# AmbaSat-1_Satellite.net
KiCad netlist of a schematic drawn in EAGLE
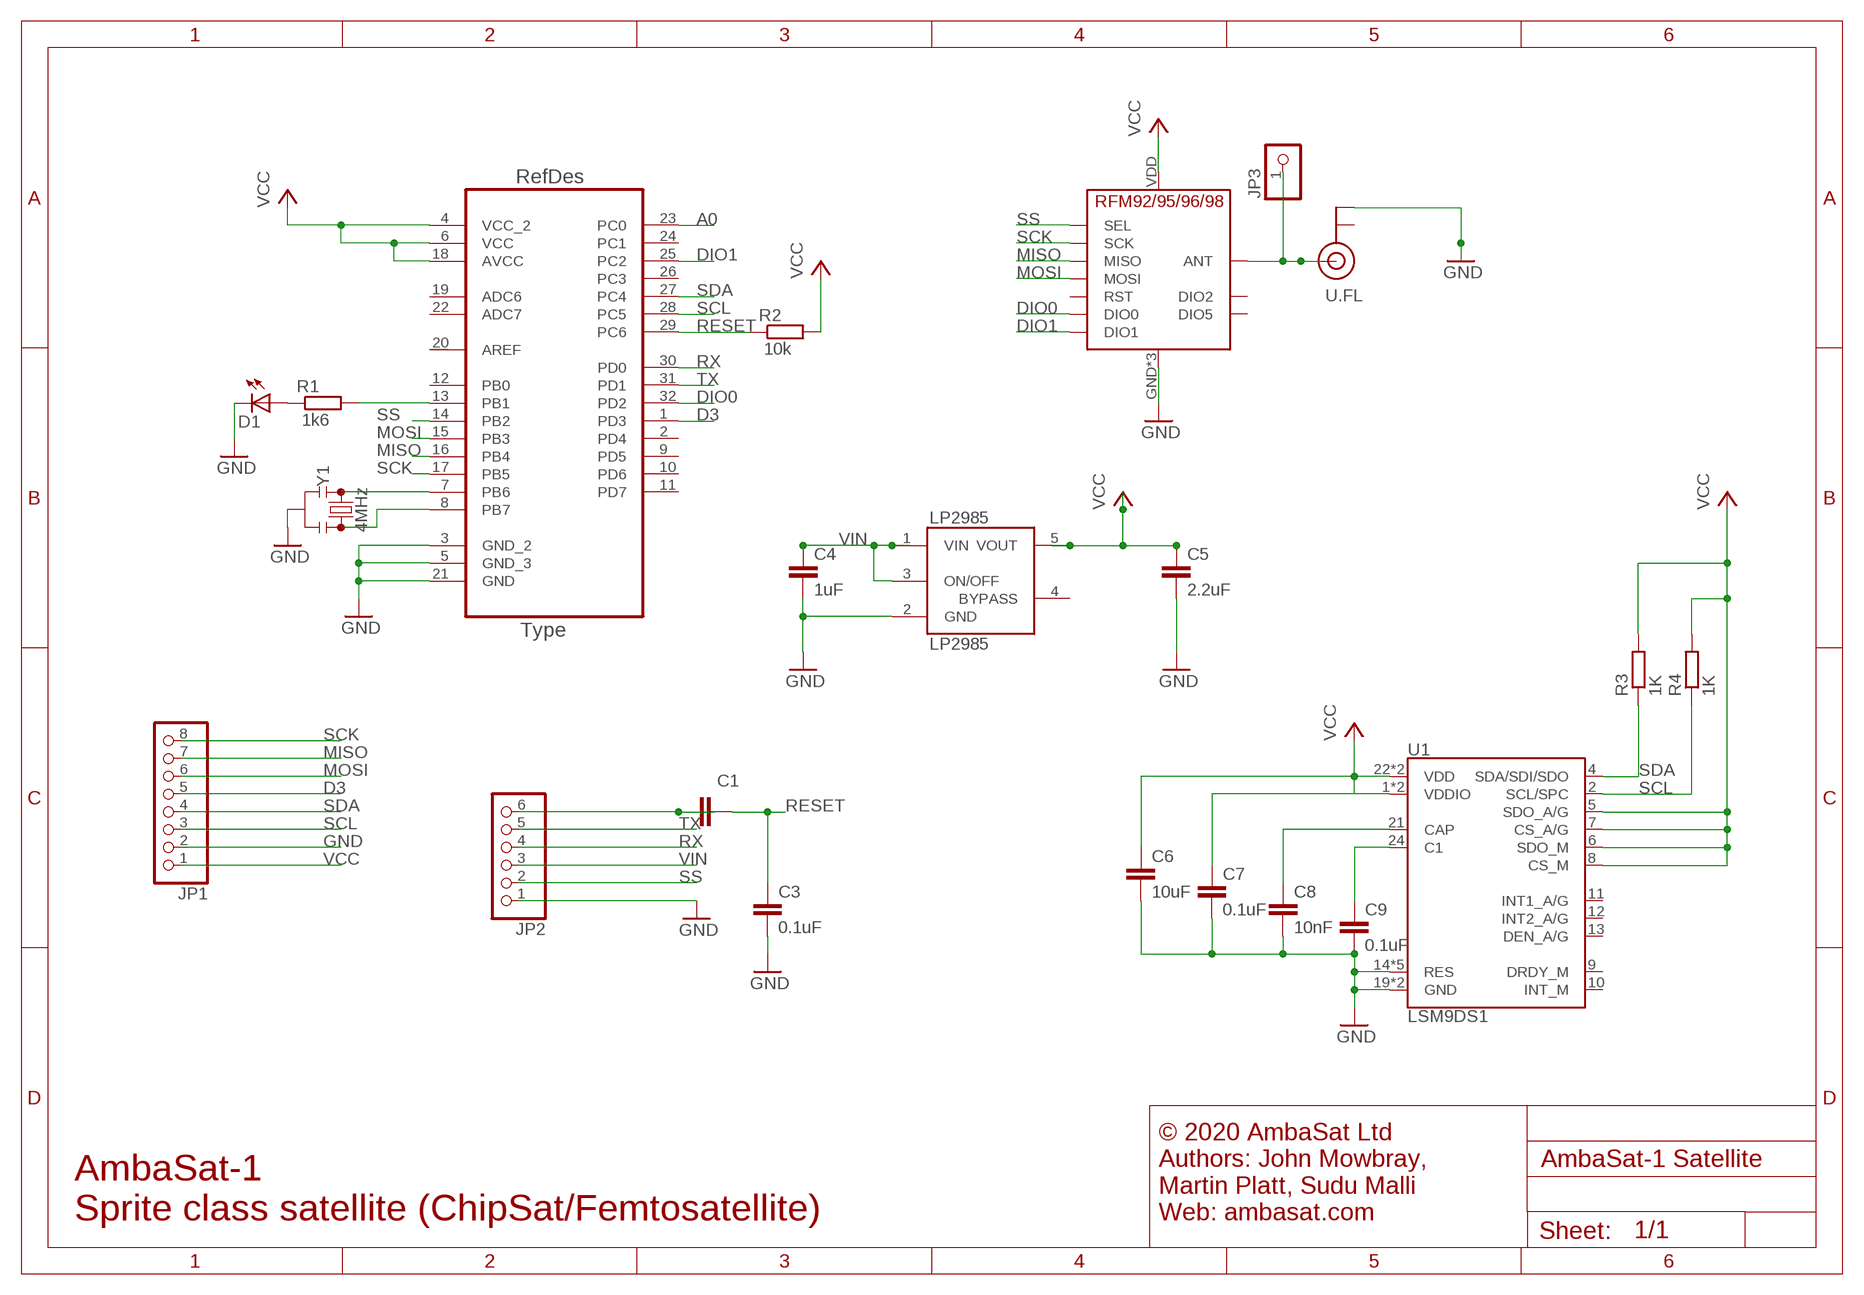
[diagram p0: schematic, sheet 1]

(export (version "E")
  (design (tool "Eeschema 10.0.6"))
  (components
    (comp (ref "ATMEGA328P-AU")
      (value "ATMEGA328P-AU")
      (footprint "eagle-import:QFP80P900X900X120-32N")
      (libsource (lib "eagle-import") (part "ATMEGA328P-AU"))
    )
    (comp (ref "C1")
      (value "1uF")
      (footprint "eagle-import:C0805K")
      (libsource (lib "eagle-import") (part "C-EUC0805K"))
    )
    (comp (ref "C3")
      (value "0.1uF")
      (footprint "eagle-import:C0805K")
      (libsource (lib "eagle-import") (part "C-EUC0805K"))
    )
    (comp (ref "C4")
      (value "1uF")
      (footprint "eagle-import:C0805K")
      (libsource (lib "eagle-import") (part "C-EUC0805K"))
    )
    (comp (ref "C5")
      (value "2.2uF")
      (footprint "eagle-import:C0805K")
      (libsource (lib "eagle-import") (part "C-EUC0805K"))
    )
    (comp (ref "C6")
      (value "10uF")
      (footprint "eagle-import:C0805K")
      (libsource (lib "eagle-import") (part "C-EUC0805K"))
    )
    (comp (ref "C7")
      (value "0.1uF")
      (footprint "eagle-import:C0805K")
      (libsource (lib "eagle-import") (part "C-EUC0805K"))
    )
    (comp (ref "C8")
      (value "10nF")
      (footprint "eagle-import:C0805K")
      (libsource (lib "eagle-import") (part "C-EUC0805K"))
    )
    (comp (ref "C9")
      (value "0.1uF")
      (footprint "eagle-import:C0805K")
      (libsource (lib "eagle-import") (part "C-EUC0805K"))
    )
    (comp (ref "D1")
      (value "LEDCHIP-LED0805")
      (footprint "eagle-import:CHIP-LED0805")
      (libsource (lib "eagle-import") (part "LEDCHIP-LED0805"))
    )
    (comp (ref "JP1")
      (value "PINHD-1X8")
      (footprint "eagle-import:1X08")
      (libsource (lib "eagle-import") (part "PINHD-1X8"))
    )
    (comp (ref "JP2")
      (value "PINHD-1X6")
      (footprint "eagle-import:1X06")
      (libsource (lib "eagle-import") (part "PINHD-1X6"))
    )
    (comp (ref "JP3")
      (value "HEADER-1X1ROUND")
      (footprint "eagle-import:1X01_ROUND")
      (libsource (lib "eagle-import") (part "HEADER-1X1ROUND"))
    )
    (comp (ref "LP2985")
      (value "LP2985AIM5-3.3")
      (footprint "eagle-import:SOT25")
      (libsource (lib "eagle-import") (part "LP2985AIM5-3.3"))
    )
    (comp (ref "R1")
      (value "1k6")
      (footprint "eagle-import:M0805")
      (libsource (lib "eagle-import") (part "R-EU_M0805"))
    )
    (comp (ref "R2")
      (value "10k")
      (footprint "eagle-import:M0805")
      (libsource (lib "eagle-import") (part "R-EU_M0805"))
    )
    (comp (ref "R3")
      (value "1K")
      (footprint "eagle-import:M0805")
      (libsource (lib "eagle-import") (part "R-EU_M0805"))
    )
    (comp (ref "R4")
      (value "1K")
      (footprint "eagle-import:M0805")
      (libsource (lib "eagle-import") (part "R-EU_M0805"))
    )
    (comp (ref "RFM95")
      (value "RFM95")
      (footprint "eagle-import:RFM95")
      (libsource (lib "eagle-import") (part "RFM95"))
    )
    (comp (ref "U.FL")
      (value "U.FL")
      (footprint "eagle-import:U.FL")
      (libsource (lib "eagle-import") (part "U.FL"))
    )
    (comp (ref "U1")
      (value "LSM9DS1")
      (footprint "eagle-import:LGA24-8X4")
      (libsource (lib "eagle-import") (part "LSM9DS1"))
    )
    (comp (ref "Y1")
      (value "4MHz")
      (footprint "eagle-import:RESONATOR-SMD-4.5X2.0")
      (libsource (lib "eagle-import") (part "RESONATOR-4MHZSMD-4.5X2"))
    )
  )
  (nets
    (net (code "1") (name "/A0") (class "Default")
      (node (ref "ATMEGA328P-AU") (pin "23") (pinfunction "PC0_23") (pintype "bidirectional"))
    )
    (net (code "2") (name "/BYPASS") (class "Default")
      (node (ref "LP2985") (pin "4") (pinfunction "BYPASS_4") (pintype "power_in"))
    )
    (net (code "3") (name "/D3") (class "Default")
      (node (ref "ATMEGA328P-AU") (pin "1") (pinfunction "PD3_1") (pintype "bidirectional"))
      (node (ref "JP1") (pin "5") (pinfunction "5_5") (pintype "passive"))
    )
    (net (code "4") (name "/DIO0") (class "Default")
      (node (ref "ATMEGA328P-AU") (pin "32") (pinfunction "PD2_32") (pintype "bidirectional"))
      (node (ref "RFM95") (pin "DIO0") (pinfunction "DIO0_DIO0") (pintype "open_collector"))
    )
    (net (code "5") (name "/DIO1") (class "Default")
      (node (ref "ATMEGA328P-AU") (pin "25") (pinfunction "PC2_25") (pintype "bidirectional"))
      (node (ref "RFM95") (pin "DIO1") (pinfunction "DIO1_DIO1") (pintype "open_collector"))
    )
    (net (code "6") (name "/MISO") (class "Default")
      (node (ref "ATMEGA328P-AU") (pin "16") (pinfunction "PB4_16") (pintype "bidirectional"))
      (node (ref "JP1") (pin "7") (pinfunction "7_7") (pintype "passive"))
      (node (ref "RFM95") (pin "MISO") (pinfunction "MISO_MISO") (pintype "input"))
    )
    (net (code "7") (name "/MOSI") (class "Default")
      (node (ref "ATMEGA328P-AU") (pin "15") (pinfunction "PB3_15") (pintype "bidirectional"))
      (node (ref "JP1") (pin "6") (pinfunction "6_6") (pintype "passive"))
      (node (ref "RFM95") (pin "MOSI") (pinfunction "MOSI_MOSI") (pintype "output"))
    )
    (net (code "8") (name "/RESET") (class "Default")
      (node (ref "ATMEGA328P-AU") (pin "29") (pinfunction "PC6_29") (pintype "bidirectional"))
      (node (ref "C1") (pin "1") (pinfunction "1_1") (pintype "passive"))
      (node (ref "C3") (pin "1") (pinfunction "1_1") (pintype "passive"))
      (node (ref "R2") (pin "1") (pinfunction "1_1") (pintype "passive"))
    )
    (net (code "9") (name "/RX") (class "Default")
      (node (ref "ATMEGA328P-AU") (pin "30") (pinfunction "PD0_30") (pintype "bidirectional"))
      (node (ref "JP2") (pin "4") (pinfunction "4_4") (pintype "passive"))
    )
    (net (code "10") (name "/SCK") (class "Default")
      (node (ref "ATMEGA328P-AU") (pin "17") (pinfunction "PB5_17") (pintype "bidirectional"))
      (node (ref "JP1") (pin "8") (pinfunction "8_8") (pintype "passive"))
      (node (ref "RFM95") (pin "SCK") (pinfunction "SCK_SCK") (pintype "input"))
    )
    (net (code "11") (name "/SCL") (class "Default")
      (node (ref "ATMEGA328P-AU") (pin "28") (pinfunction "PC5_28") (pintype "bidirectional"))
      (node (ref "JP1") (pin "3") (pinfunction "3_3") (pintype "passive"))
      (node (ref "R4") (pin "1") (pinfunction "1_1") (pintype "passive"))
      (node (ref "U1") (pin "2") (pinfunction "SCL/SPC_2") (pintype "bidirectional"))
    )
    (net (code "12") (name "/SDA") (class "Default")
      (node (ref "ATMEGA328P-AU") (pin "27") (pinfunction "PC4_27") (pintype "bidirectional"))
      (node (ref "JP1") (pin "4") (pinfunction "4_4") (pintype "passive"))
      (node (ref "R3") (pin "1") (pinfunction "1_1") (pintype "passive"))
      (node (ref "U1") (pin "4") (pinfunction "SDA/SDI/SDO_4") (pintype "bidirectional"))
    )
    (net (code "13") (name "/SS") (class "Default")
      (node (ref "ATMEGA328P-AU") (pin "14") (pinfunction "PB2_14") (pintype "bidirectional"))
      (node (ref "JP2") (pin "2") (pinfunction "2_2") (pintype "passive"))
      (node (ref "RFM95") (pin "NSS") (pinfunction "SEL_NSS") (pintype "input"))
    )
    (net (code "14") (name "/TX") (class "Default")
      (node (ref "ATMEGA328P-AU") (pin "31") (pinfunction "PD1_31") (pintype "bidirectional"))
      (node (ref "JP2") (pin "5") (pinfunction "5_5") (pintype "passive"))
    )
    (net (code "15") (name "/VIN") (class "Default")
      (node (ref "C4") (pin "1") (pinfunction "1_1") (pintype "passive"))
      (node (ref "JP2") (pin "3") (pinfunction "3_3") (pintype "passive"))
      (node (ref "LP2985") (pin "1") (pinfunction "VIN_1") (pintype "power_in"))
      (node (ref "LP2985") (pin "3") (pinfunction "ON/OFF_3") (pintype "input"))
    )
    (net (code "16") (name "GND") (class "Default")
      (node (ref "ATMEGA328P-AU") (pin "21") (pinfunction "GND_21") (pintype "passive"))
      (node (ref "ATMEGA328P-AU") (pin "3") (pinfunction "GND_2_3") (pintype "passive"))
      (node (ref "ATMEGA328P-AU") (pin "5") (pinfunction "GND_3_5") (pintype "passive"))
      (node (ref "C3") (pin "2") (pinfunction "2_2") (pintype "passive"))
      (node (ref "C4") (pin "2") (pinfunction "2_2") (pintype "passive"))
      (node (ref "C5") (pin "2") (pinfunction "2_2") (pintype "passive"))
      (node (ref "C6") (pin "2") (pinfunction "2_2") (pintype "passive"))
      (node (ref "C7") (pin "2") (pinfunction "2_2") (pintype "passive"))
      (node (ref "C8") (pin "2") (pinfunction "2_2") (pintype "passive"))
      (node (ref "C9") (pin "2") (pinfunction "2_2") (pintype "passive"))
      (node (ref "D1") (pin "C") (pinfunction "C_C") (pintype "passive"))
      (node (ref "JP1") (pin "2") (pinfunction "2_2") (pintype "passive"))
      (node (ref "JP2") (pin "1") (pinfunction "1_1") (pintype "passive"))
      (node (ref "LP2985") (pin "2") (pinfunction "GND_2") (pintype "power_in"))
      (node (ref "RFM95") (pin "GND") (pinfunction "GND_GND") (pintype "power_in"))
      (node (ref "RFM95") (pin "GND1") (pinfunction "GND_GND1") (pintype "power_in"))
      (node (ref "RFM95") (pin "GND2") (pinfunction "GND_GND2") (pintype "power_in"))
      (node (ref "U.FL") (pin "2") (pinfunction "GND_2") (pintype "bidirectional"))
      (node (ref "U1") (pin "14") (pinfunction "RES_14") (pintype "bidirectional"))
      (node (ref "U1") (pin "15") (pinfunction "RES_15") (pintype "bidirectional"))
      (node (ref "U1") (pin "16") (pinfunction "RES_16") (pintype "bidirectional"))
      (node (ref "U1") (pin "17") (pinfunction "RES_17") (pintype "bidirectional"))
      (node (ref "U1") (pin "18") (pinfunction "RES_18") (pintype "bidirectional"))
      (node (ref "U1") (pin "19") (pinfunction "GND_19") (pintype "bidirectional"))
      (node (ref "U1") (pin "20") (pinfunction "GND_20") (pintype "bidirectional"))
      (node (ref "Y1") (pin "2") (pinfunction "2_2") (pintype "passive"))
    )
    (net (code "17") (name "Net-(ATMEGA328P-AU-PB1)") (class "Default")
      (node (ref "ATMEGA328P-AU") (pin "13") (pinfunction "PB1_13") (pintype "bidirectional"))
      (node (ref "R1") (pin "2") (pinfunction "2_2") (pintype "passive"))
    )
    (net (code "18") (name "Net-(ATMEGA328P-AU-PB6)") (class "Default")
      (node (ref "ATMEGA328P-AU") (pin "7") (pinfunction "PB6_7") (pintype "bidirectional"))
      (node (ref "Y1") (pin "1") (pinfunction "1_1") (pintype "passive"))
    )
    (net (code "19") (name "Net-(ATMEGA328P-AU-PB7)") (class "Default")
      (node (ref "ATMEGA328P-AU") (pin "8") (pinfunction "PB7_8") (pintype "bidirectional"))
      (node (ref "Y1") (pin "3") (pinfunction "3_3") (pintype "passive"))
    )
    (net (code "20") (name "Net-(C1-Pad2)") (class "Default")
      (node (ref "C1") (pin "2") (pinfunction "2_2") (pintype "passive"))
      (node (ref "JP2") (pin "6") (pinfunction "6_6") (pintype "passive"))
    )
    (net (code "21") (name "Net-(D1-PadA)") (class "Default")
      (node (ref "D1") (pin "A") (pinfunction "A_A") (pintype "passive"))
      (node (ref "R1") (pin "1") (pinfunction "1_1") (pintype "passive"))
    )
    (net (code "22") (name "Net-(U.FL-SIGNAL)") (class "Default")
      (node (ref "JP3") (pin "1") (pinfunction "1_1") (pintype "passive"))
      (node (ref "RFM95") (pin "ANT") (pinfunction "ANT_ANT") (pintype "passive"))
      (node (ref "U.FL") (pin "FEED") (pinfunction "SIGNAL_FEED") (pintype "bidirectional"))
    )
    (net (code "23") (name "Net-(U1-C1)") (class "Default")
      (node (ref "C9") (pin "1") (pinfunction "1_1") (pintype "passive"))
      (node (ref "U1") (pin "24") (pinfunction "C1_24") (pintype "bidirectional"))
    )
    (net (code "24") (name "Net-(U1-CAP)") (class "Default")
      (node (ref "C8") (pin "1") (pinfunction "1_1") (pintype "passive"))
      (node (ref "U1") (pin "21") (pinfunction "CAP_21") (pintype "bidirectional"))
    )
    (net (code "25") (name "VCC") (class "Default")
      (node (ref "ATMEGA328P-AU") (pin "18") (pinfunction "AVCC_18") (pintype "power_in"))
      (node (ref "ATMEGA328P-AU") (pin "4") (pinfunction "VCC_2_4") (pintype "power_in"))
      (node (ref "ATMEGA328P-AU") (pin "6") (pinfunction "VCC_6") (pintype "power_in"))
      (node (ref "C5") (pin "1") (pinfunction "1_1") (pintype "passive"))
      (node (ref "C6") (pin "1") (pinfunction "1_1") (pintype "passive"))
      (node (ref "C7") (pin "1") (pinfunction "1_1") (pintype "passive"))
      (node (ref "JP1") (pin "1") (pinfunction "1_1") (pintype "passive"))
      (node (ref "LP2985") (pin "5") (pinfunction "VOUT_5") (pintype "power_in"))
      (node (ref "R2") (pin "2") (pinfunction "2_2") (pintype "passive"))
      (node (ref "R3") (pin "2") (pinfunction "2_2") (pintype "passive"))
      (node (ref "R4") (pin "2") (pinfunction "2_2") (pintype "passive"))
      (node (ref "RFM95") (pin "VDD") (pinfunction "VCC_VDD") (pintype "power_in"))
      (node (ref "U1") (pin "1") (pinfunction "VDDIO_1") (pintype "bidirectional"))
      (node (ref "U1") (pin "22") (pinfunction "VDD_22") (pintype "bidirectional"))
      (node (ref "U1") (pin "23") (pinfunction "VDD_23") (pintype "bidirectional"))
      (node (ref "U1") (pin "3") (pinfunction "VDDIO_3") (pintype "bidirectional"))
      (node (ref "U1") (pin "5") (pinfunction "SDO_A/G_5") (pintype "bidirectional"))
      (node (ref "U1") (pin "6") (pinfunction "SDO_M_6") (pintype "bidirectional"))
      (node (ref "U1") (pin "7") (pinfunction "CS_A/G_7") (pintype "bidirectional"))
      (node (ref "U1") (pin "8") (pinfunction "CS_M_8") (pintype "bidirectional"))
    )
    (net (code "26") (name "unconnected-(ATMEGA328P-AU-ADC6-Pad19)") (class "Default")
      (node (ref "ATMEGA328P-AU") (pin "19") (pinfunction "ADC6_19") (pintype "input"))
    )
    (net (code "27") (name "unconnected-(ATMEGA328P-AU-ADC7-Pad22)") (class "Default")
      (node (ref "ATMEGA328P-AU") (pin "22") (pinfunction "ADC7_22") (pintype "input"))
    )
    (net (code "28") (name "unconnected-(ATMEGA328P-AU-AREF-Pad20)") (class "Default")
      (node (ref "ATMEGA328P-AU") (pin "20") (pinfunction "AREF_20") (pintype "input"))
    )
    (net (code "29") (name "unconnected-(ATMEGA328P-AU-PB0-Pad12)") (class "Default")
      (node (ref "ATMEGA328P-AU") (pin "12") (pinfunction "PB0_12") (pintype "bidirectional"))
    )
    (net (code "30") (name "unconnected-(ATMEGA328P-AU-PC1-Pad24)") (class "Default")
      (node (ref "ATMEGA328P-AU") (pin "24") (pinfunction "PC1_24") (pintype "bidirectional"))
    )
    (net (code "31") (name "unconnected-(ATMEGA328P-AU-PC3-Pad26)") (class "Default")
      (node (ref "ATMEGA328P-AU") (pin "26") (pinfunction "PC3_26") (pintype "bidirectional"))
    )
    (net (code "32") (name "unconnected-(ATMEGA328P-AU-PD4-Pad2)") (class "Default")
      (node (ref "ATMEGA328P-AU") (pin "2") (pinfunction "PD4_2") (pintype "bidirectional"))
    )
    (net (code "33") (name "unconnected-(ATMEGA328P-AU-PD5-Pad9)") (class "Default")
      (node (ref "ATMEGA328P-AU") (pin "9") (pinfunction "PD5_9") (pintype "bidirectional"))
    )
    (net (code "34") (name "unconnected-(ATMEGA328P-AU-PD6-Pad10)") (class "Default")
      (node (ref "ATMEGA328P-AU") (pin "10") (pinfunction "PD6_10") (pintype "bidirectional"))
    )
    (net (code "35") (name "unconnected-(ATMEGA328P-AU-PD7-Pad11)") (class "Default")
      (node (ref "ATMEGA328P-AU") (pin "11") (pinfunction "PD7_11") (pintype "bidirectional"))
    )
    (net (code "36") (name "unconnected-(RFM95-PadDIO2)") (class "Default")
      (node (ref "RFM95") (pin "DIO2") (pinfunction "DIO2_DIO2") (pintype "open_collector"))
    )
    (net (code "37") (name "unconnected-(RFM95-PadDIO5)") (class "Default")
      (node (ref "RFM95") (pin "DIO5") (pinfunction "DIO5_DIO5") (pintype "open_collector"))
    )
    (net (code "38") (name "unconnected-(RFM95-PadRST)") (class "Default")
      (node (ref "RFM95") (pin "RST") (pinfunction "RST_RST") (pintype "open_collector"))
    )
    (net (code "39") (name "unconnected-(U.FL-GND-Pad1)") (class "Default")
      (node (ref "U.FL") (pin "1") (pinfunction "GND_1") (pintype "bidirectional"))
    )
    (net (code "40") (name "unconnected-(U1-DEN_A{slash}G-Pad13)") (class "Default")
      (node (ref "U1") (pin "13") (pinfunction "DEN_A/G_13") (pintype "bidirectional"))
    )
    (net (code "41") (name "unconnected-(U1-DRDY_M-Pad9)") (class "Default")
      (node (ref "U1") (pin "9") (pinfunction "DRDY_M_9") (pintype "bidirectional"))
    )
    (net (code "42") (name "unconnected-(U1-INT1_A{slash}G-Pad11)") (class "Default")
      (node (ref "U1") (pin "11") (pinfunction "INT1_A/G_11") (pintype "bidirectional"))
    )
    (net (code "43") (name "unconnected-(U1-INT2_A{slash}G-Pad12)") (class "Default")
      (node (ref "U1") (pin "12") (pinfunction "INT2_A/G_12") (pintype "bidirectional"))
    )
    (net (code "44") (name "unconnected-(U1-INT_M-Pad10)") (class "Default")
      (node (ref "U1") (pin "10") (pinfunction "INT_M_10") (pintype "bidirectional"))
    )
  )
)
